# Rechargeable_Circuit.net
KiCad netlist of a schematic drawn in Altium Designer
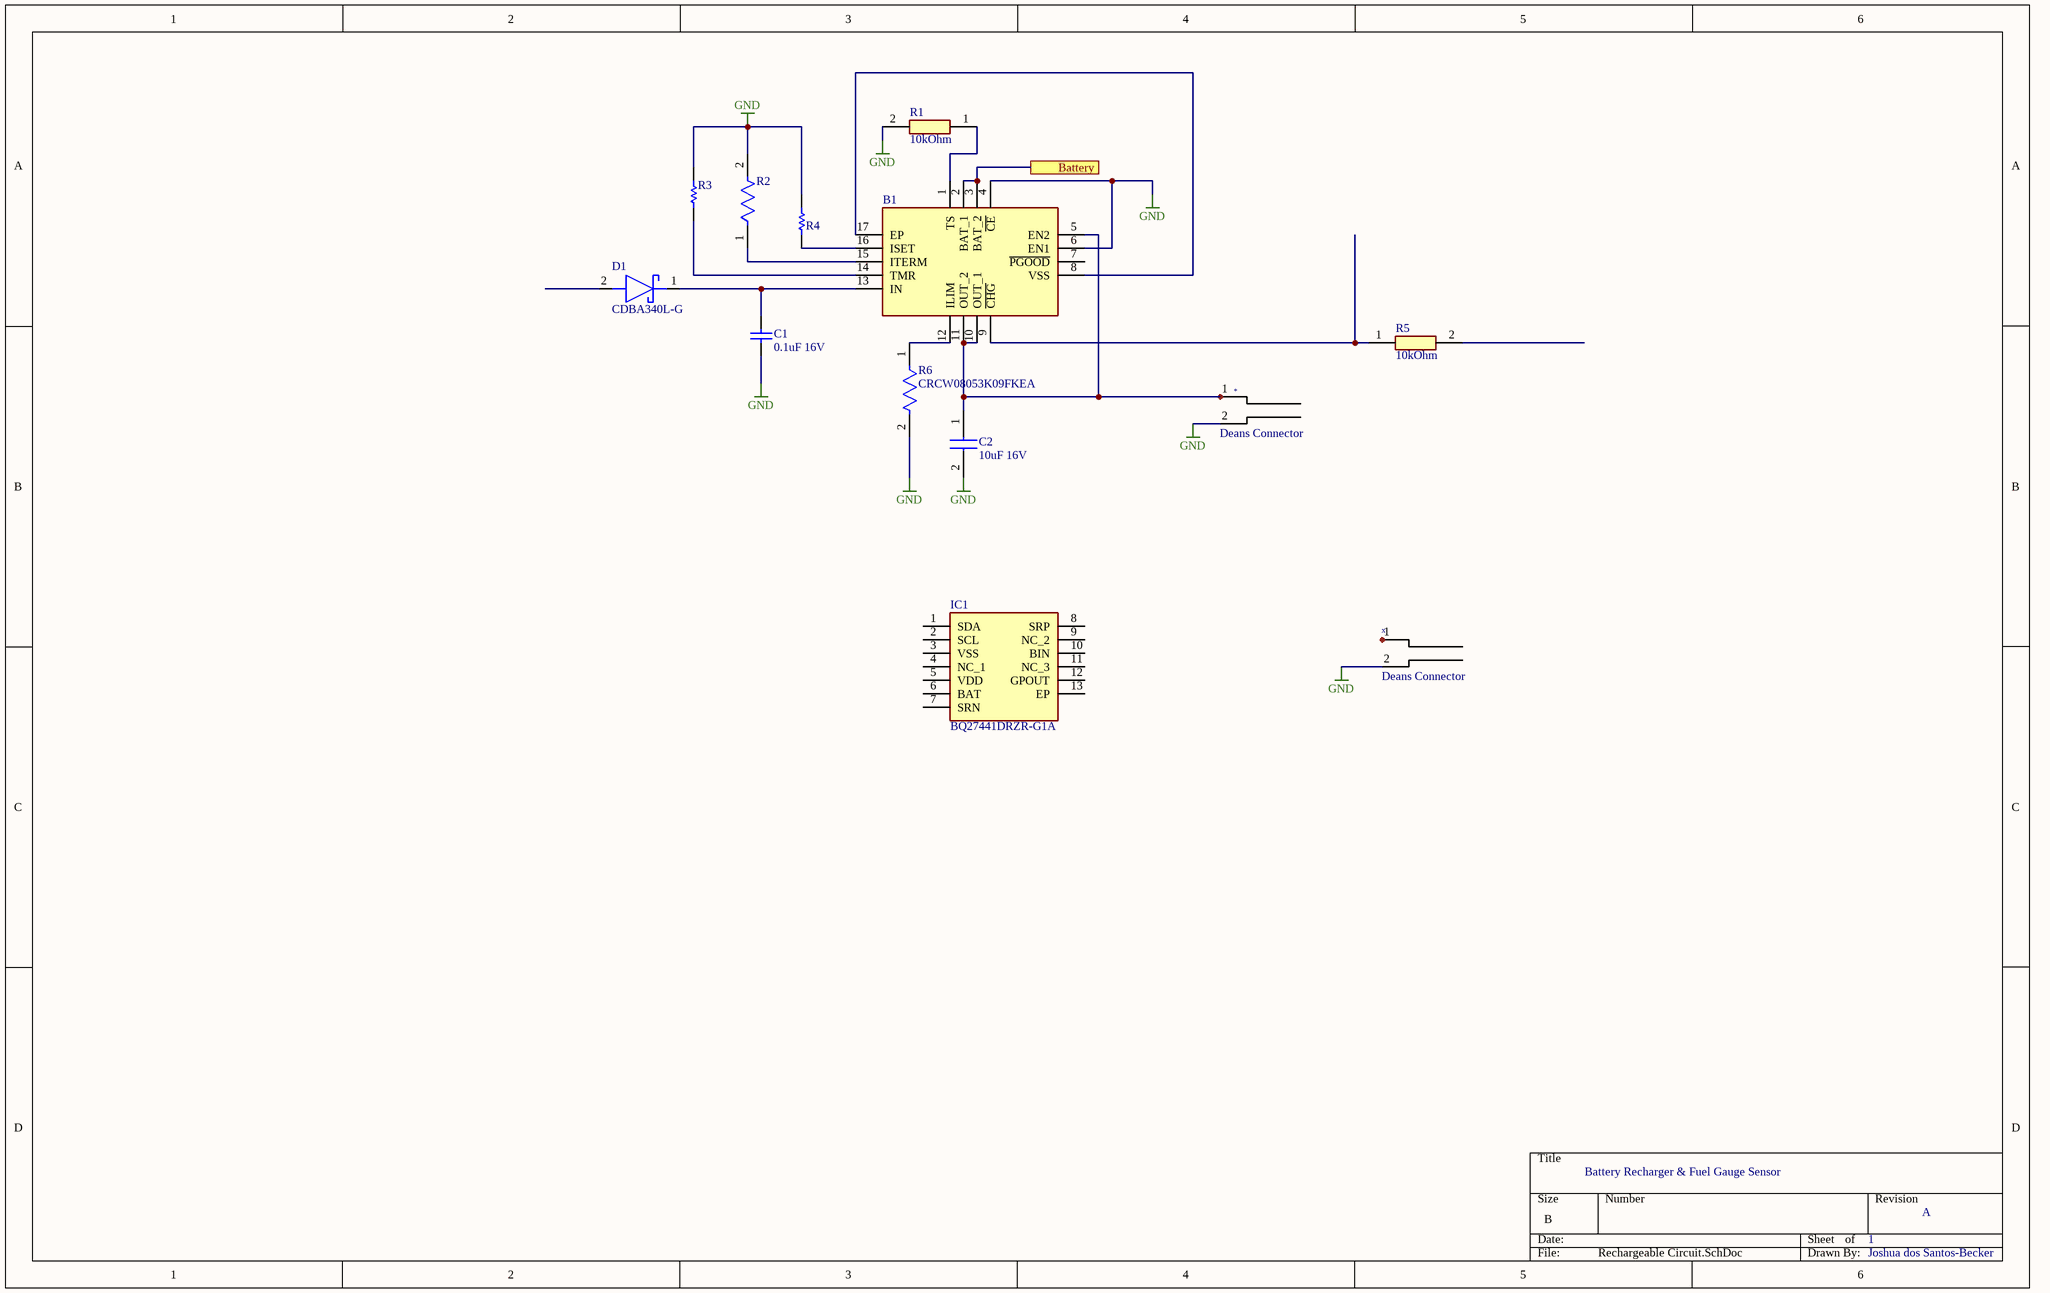
[diagram p0: Rechargeable Circuit.SchDoc]

(export (version "E")
  (design (tool "Eeschema 10.0.6"))
  (components
    (comp (ref "*")
      (value "Deans Connector")
      (footprint "Deans")
      (libsource (lib "gsl") (part "Deans Connector"))
    )
    (comp (ref "B1")
      (value "BQ24232HRGTR")
      (footprint "QFN50P300X300X100-17N-D")
      (description "USB-Friendly Lithium Based Battery Charger With Power-Path For 4.35V Batteries")
      (fields (field (name "MOUSER PART NUMBER") "595-BQ24232HRGTR"))
      (libsource (lib "gsl") (part "BQ24232HRGTR"))
    )
    (comp (ref "C1")
      (value "0.1uF 16V")
      (footprint "CAPC2113X100X50ML30T10")
      (description "C0805X104K4RACTU")
      (fields (field (name "MANUFACTURER") "Kemet"))
      (libsource (lib "Altium Content Vault") (part "CAP"))
    )
    (comp (ref "C2")
      (value "10uF 16V")
      (footprint "SamacSys:GRM32DR61C106KA01L")
      (description "GRM32DR71C106KA01L")
      (fields (field (name "MOUSER PART NUMBER") "81-GRM32R71C106KA01L"))
      (libsource (lib "*") (part "GRM32DR71C106KA01L"))
    )
    (comp (ref "D1")
      (value "CDBA340L-G")
      (footprint "SamacSys:DIONM5127X229N")
      (description "Schottky Diode")
      (fields (field (name "MOUSER PART NUMBER") "750-CDBA340L-G"))
      (libsource (lib "gsl") (part "CDBA340L-G"))
    )
    (comp (ref "IC1")
      (value "BQ27441DRZR-G1A")
      (footprint "SamacSys:BQ27441DRZRG1A")
      (description "Integrated Circuit")
      (fields (field (name "MOUSER PART NUMBER") "595-BQ27441DRZR-G1A"))
      (libsource (lib "*") (part "BQ27441DRZR-G1A"))
    )
    (comp (ref "R1")
      (value "10kOhm")
      (footprint "SamacSys:RESC6331X80N")
      (description "Resistor")
      (fields
        (field (name "MANUFACTURER_PART_NUMBER") "CRM2512QJW-103ELF")
        (field (name "MOUSER PART NUMBER") "652-CRM2512QJW-103E")
      )
      (libsource (lib "*") (part "CRM2512QJW-103ELF"))
    )
    (comp (ref "R2")
      (value "RG2012V-1431-B-T5")
      (footprint "FP-RG2012-MFG")
      (description "Automotive Metal Thin Film Chip Resistor, 0805, 1.43kΩ, 0.1%, 5ppm/°C, 0.125W, 150V")
      (fields (field (name "TOLERANCE") "0.1%"))
      (libsource (lib "Altium Content Vault") (part "1029c3af85768c4190bb7ad29bc67b5"))
    )
    (comp (ref "R3")
      (value "CRCW120656K2FKEA")
      (footprint "RESC3216X60X45ML10T20")
      (fields (field (name "MANUFACTURER") "Vishay Dale"))
      (libsource (lib "Altium Content Vault") (part "RES"))
    )
    (comp (ref "R4")
      (value "1K74 1% 2010(5025)")
      (footprint "RESC2010(5025)_L")
      (description "1K74 0.75W 1% 2010 (5025 Metric)  SMD")
      (fields (field (name "POWER") "0.75 W") (field (name "TOLERANCE") "1 %"))
      (libsource (lib "Altium Content Vault") (part "RES"))
    )
    (comp (ref "R5")
      (value "10kOhm")
      (footprint "SamacSys:RESC6331X80N")
      (description "Resistor")
      (fields
        (field (name "MANUFACTURER_PART_NUMBER") "CRM2512QJW-103ELF")
        (field (name "MOUSER PART NUMBER") "652-CRM2512QJW-103E")
      )
      (libsource (lib "") (part "CRM2512QJW-103ELF_1"))
    )
    (comp (ref "R6")
      (value "CRCW08053K09FKEA")
      (footprint "FP-CRCW0805-e3-IPC_C")
      (description "RES Thick Film, 3.09kΩ, 1%, 0.125W, 100ppm/°C, 0805")
      (fields (field (name "TOLERANCE") "1%"))
      (libsource (lib "Altium Content Vault") (part "1029c3af85768c4190bb7ad29bc67b5"))
    )
    (comp (ref "x")
      (value "Deans Connector")
      (footprint "Deans")
      (libsource (lib "gsl") (part "Deans Connector"))
    )
  )
  (nets
    (net (code "1") (name "/Battery") (class "Default")
      (node (ref "B1") (pin "2") (pinfunction "BAT_1_2") (pintype "passive"))
      (node (ref "B1") (pin "3") (pinfunction "BAT_2_3") (pintype "passive"))
    )
    (net (code "2") (name "GND") (class "Default")
      (node (ref "*") (pin "2") (pinfunction "2_2") (pintype "passive"))
      (node (ref "B1") (pin "4") (pinfunction "~{CE}_4") (pintype "passive"))
      (node (ref "B1") (pin "6") (pinfunction "EN1_6") (pintype "passive"))
      (node (ref "C1") (pin "2") (pinfunction "2_2") (pintype "passive"))
      (node (ref "C2") (pin "2") (pinfunction "2_2") (pintype "passive"))
      (node (ref "R1") (pin "2") (pinfunction "2_2") (pintype "passive"))
      (node (ref "R2") (pin "2") (pinfunction "2_2") (pintype "passive"))
      (node (ref "R3") (pin "1") (pinfunction "1_1") (pintype "passive"))
      (node (ref "R4") (pin "2") (pinfunction "2_2") (pintype "passive"))
      (node (ref "R6") (pin "2") (pinfunction "2_2") (pintype "passive"))
      (node (ref "x") (pin "2") (pinfunction "2_2") (pintype "passive"))
    )
    (net (code "3") (name "Net-(B1-EN2)") (class "Default")
      (node (ref "*") (pin "1") (pinfunction "1_1") (pintype "passive"))
      (node (ref "B1") (pin "10") (pinfunction "OUT_1_10") (pintype "passive"))
      (node (ref "B1") (pin "11") (pinfunction "OUT_2_11") (pintype "passive"))
      (node (ref "B1") (pin "5") (pinfunction "EN2_5") (pintype "passive"))
      (node (ref "C2") (pin "1") (pinfunction "1_1") (pintype "passive"))
    )
    (net (code "4") (name "Net-(B1-EP)") (class "Default")
      (node (ref "B1") (pin "17") (pinfunction "EP_17") (pintype "passive"))
      (node (ref "B1") (pin "8") (pinfunction "VSS_8") (pintype "passive"))
    )
    (net (code "5") (name "Net-(B1-ILIM)") (class "Default")
      (node (ref "B1") (pin "12") (pinfunction "ILIM_12") (pintype "passive"))
      (node (ref "R6") (pin "1") (pinfunction "1_1") (pintype "passive"))
    )
    (net (code "6") (name "Net-(B1-IN)") (class "Default")
      (node (ref "B1") (pin "13") (pinfunction "IN_13") (pintype "passive"))
      (node (ref "C1") (pin "1") (pinfunction "1_1") (pintype "passive"))
      (node (ref "D1") (pin "1") (pinfunction "K_1") (pintype "passive"))
    )
    (net (code "7") (name "Net-(B1-ISET)") (class "Default")
      (node (ref "B1") (pin "16") (pinfunction "ISET_16") (pintype "passive"))
      (node (ref "R4") (pin "1") (pinfunction "1_1") (pintype "passive"))
    )
    (net (code "8") (name "Net-(B1-ITERM)") (class "Default")
      (node (ref "B1") (pin "15") (pinfunction "ITERM_15") (pintype "passive"))
      (node (ref "R2") (pin "1") (pinfunction "1_1") (pintype "passive"))
    )
    (net (code "9") (name "Net-(B1-TMR)") (class "Default")
      (node (ref "B1") (pin "14") (pinfunction "TMR_14") (pintype "passive"))
      (node (ref "R3") (pin "2") (pinfunction "2_2") (pintype "passive"))
    )
    (net (code "10") (name "Net-(B1-TS)") (class "Default")
      (node (ref "B1") (pin "1") (pinfunction "TS_1") (pintype "passive"))
      (node (ref "R1") (pin "1") (pinfunction "1_1") (pintype "passive"))
    )
    (net (code "11") (name "Net-(B1-~{CHG})") (class "Default")
      (node (ref "B1") (pin "9") (pinfunction "~{CHG}_9") (pintype "passive"))
      (node (ref "R5") (pin "1") (pinfunction "1_1") (pintype "passive"))
    )
    (net (code "12") (name "unconnected-(B1-~{PGOOD}-Pad7)") (class "Default")
      (node (ref "B1") (pin "7") (pinfunction "~{PGOOD}_7") (pintype "passive"))
    )
    (net (code "13") (name "unconnected-(D1-A-Pad2)") (class "Default")
      (node (ref "D1") (pin "2") (pinfunction "A_2") (pintype "passive"))
    )
    (net (code "14") (name "unconnected-(IC1-BAT-Pad6)") (class "Default")
      (node (ref "IC1") (pin "6") (pinfunction "BAT_6") (pintype "passive"))
    )
    (net (code "15") (name "unconnected-(IC1-BIN-Pad10)") (class "Default")
      (node (ref "IC1") (pin "10") (pinfunction "BIN_10") (pintype "passive"))
    )
    (net (code "16") (name "unconnected-(IC1-EP-Pad13)") (class "Default")
      (node (ref "IC1") (pin "13") (pinfunction "EP_13") (pintype "passive"))
    )
    (net (code "17") (name "unconnected-(IC1-GPOUT-Pad12)") (class "Default")
      (node (ref "IC1") (pin "12") (pinfunction "GPOUT_12") (pintype "passive"))
    )
    (net (code "18") (name "unconnected-(IC1-NC_1-Pad4)") (class "Default")
      (node (ref "IC1") (pin "4") (pinfunction "NC_1_4") (pintype "passive"))
    )
    (net (code "19") (name "unconnected-(IC1-NC_2-Pad9)") (class "Default")
      (node (ref "IC1") (pin "9") (pinfunction "NC_2_9") (pintype "passive"))
    )
    (net (code "20") (name "unconnected-(IC1-NC_3-Pad11)") (class "Default")
      (node (ref "IC1") (pin "11") (pinfunction "NC_3_11") (pintype "passive"))
    )
    (net (code "21") (name "unconnected-(IC1-SCL-Pad2)") (class "Default")
      (node (ref "IC1") (pin "2") (pinfunction "SCL_2") (pintype "passive"))
    )
    (net (code "22") (name "unconnected-(IC1-SDA-Pad1)") (class "Default")
      (node (ref "IC1") (pin "1") (pinfunction "SDA_1") (pintype "passive"))
    )
    (net (code "23") (name "unconnected-(IC1-SRN-Pad7)") (class "Default")
      (node (ref "IC1") (pin "7") (pinfunction "SRN_7") (pintype "passive"))
    )
    (net (code "24") (name "unconnected-(IC1-SRP-Pad8)") (class "Default")
      (node (ref "IC1") (pin "8") (pinfunction "SRP_8") (pintype "passive"))
    )
    (net (code "25") (name "unconnected-(IC1-VDD-Pad5)") (class "Default")
      (node (ref "IC1") (pin "5") (pinfunction "VDD_5") (pintype "passive"))
    )
    (net (code "26") (name "unconnected-(IC1-VSS-Pad3)") (class "Default")
      (node (ref "IC1") (pin "3") (pinfunction "VSS_3") (pintype "passive"))
    )
    (net (code "27") (name "unconnected-(R5-Pad2)") (class "Default")
      (node (ref "R5") (pin "2") (pinfunction "2_2") (pintype "passive"))
    )
    (net (code "28") (name "unconnected-(x-Pad1)") (class "Default")
      (node (ref "x") (pin "1") (pinfunction "1_1") (pintype "passive"))
    )
  )
)
